# dimmer.net
KiCad netlist of a schematic drawn in Altium Designer
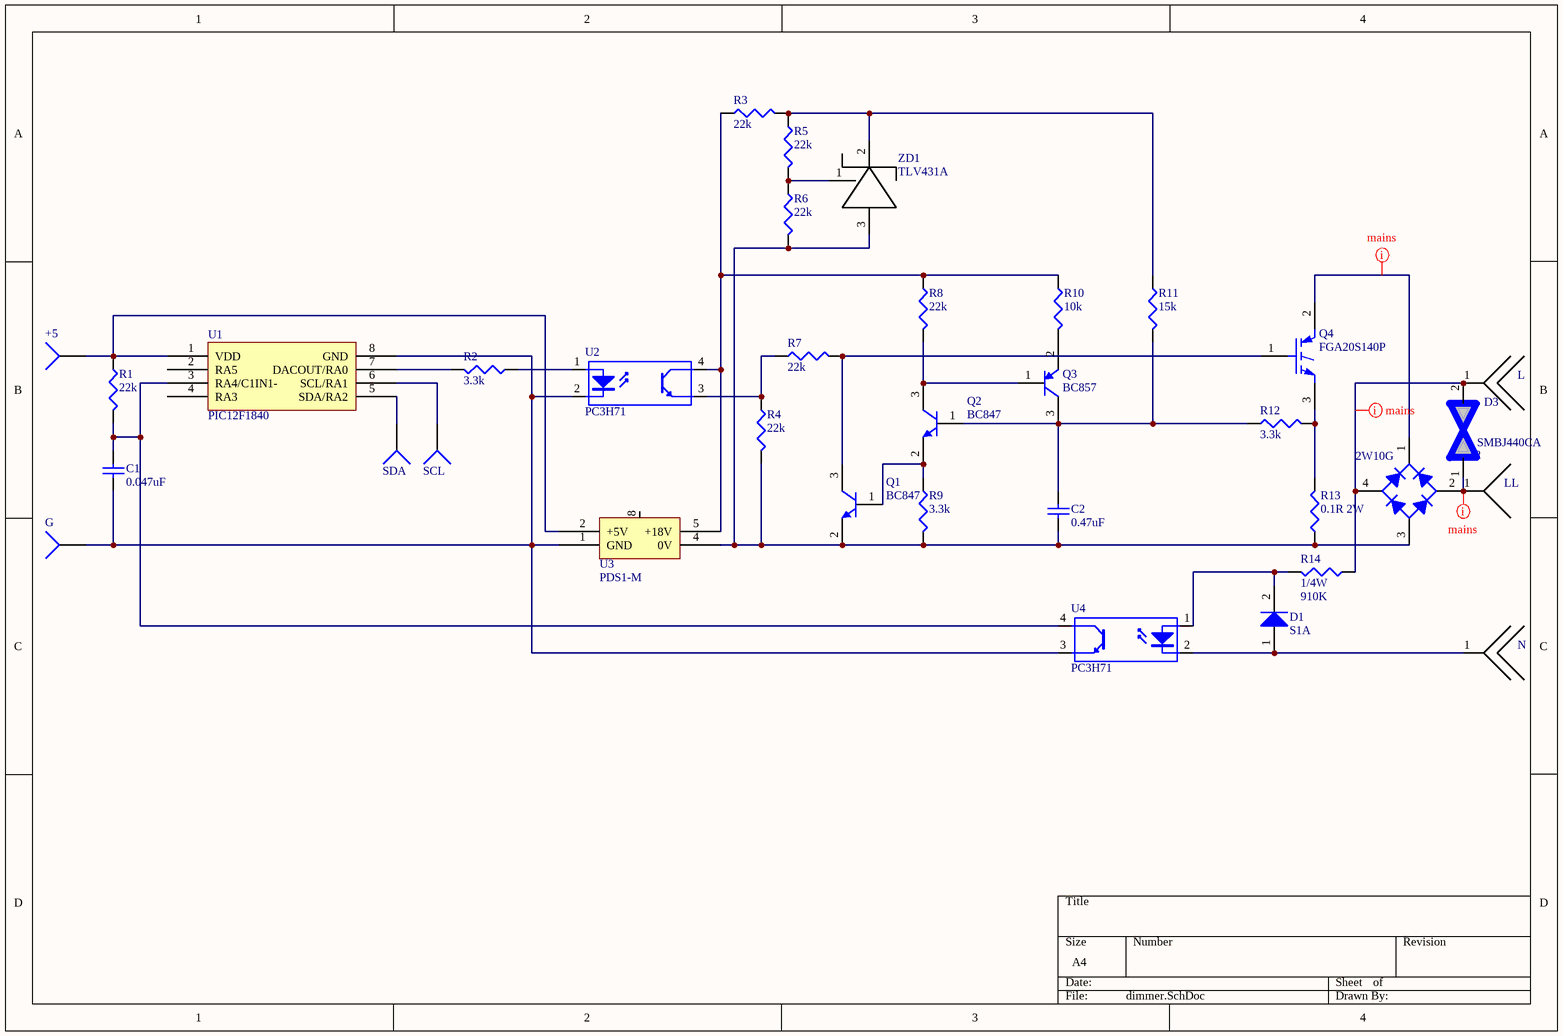
[diagram p0: dimmer.SchDoc]

(export (version "E")
  (design (tool "Eeschema 10.0.6"))
  (components
    (comp (ref "+5")
      (value "Socket")
      (footprint "PIN1")
      (fields (field (name "PUBLISHER") "Altium Limited"))
      (libsource (lib "misc") (part "Socket"))
    )
    (comp (ref "C1")
      (value "0.047uF")
      (footprint "1608[0603]")
      (description "Capacitor (Semiconductor SIM Model)")
      (fields (field (name "PUBLISHER") "Altium Limited"))
      (libsource (lib "Miscellaneous Devices") (part "Cap Semi"))
    )
    (comp (ref "C2")
      (value "0.47uF")
      (footprint "1608[0603]")
      (description "Capacitor (Semiconductor SIM Model)")
      (fields (field (name "PUBLISHER") "Altium Limited"))
      (libsource (lib "Miscellaneous Devices") (part "Cap Semi"))
    )
    (comp (ref "D1")
      (value "S1A")
      (footprint "DO-214AC")
      (description "Default Diode")
      (fields (field (name "PUBLISHER") "Altium Limited"))
      (libsource (lib "Miscellaneous Devices") (part "Diode"))
    )
    (comp (ref "D2")
      (value "2W10G")
      (footprint "2W10G")
      (description "Full Wave Diode Bridge")
      (fields (field (name "PUBLISHER") "Altium Limited"))
      (libsource (lib "Miscellaneous Devices") (part "Bridge1"))
    )
    (comp (ref "D3") (value "SMBJ440CA") (footprint "DO-214AA") (libsource (lib "tvs") (part "SMBJ440CA")))
    (comp (ref "G")
      (value "Socket")
      (footprint "PIN1")
      (fields (field (name "PUBLISHER") "Altium Limited"))
      (libsource (lib "misc") (part "Socket"))
    )
    (comp (ref "L") (value "PWRCON2X") (footprint "MAINSPIN2x") (libsource (lib "misc") (part "PWRCON2X")))
    (comp (ref "LL") (value "PWRCON") (footprint "MAINSPIN1") (libsource (lib "misc") (part "PWRCON")))
    (comp (ref "N") (value "PWRCON2X") (footprint "MAINSPIN3x") (libsource (lib "misc") (part "PWRCON2X")))
    (comp (ref "Q1")
      (value "BC847")
      (footprint "SOT-23_N")
      (description "NPN Bipolar Transistor")
      (fields (field (name "PUBLISHER") "Altium Limited"))
      (libsource (lib "Miscellaneous Devices") (part "NPN"))
    )
    (comp (ref "Q2")
      (value "BC847")
      (footprint "SOT-23_N")
      (description "NPN Bipolar Transistor")
      (fields (field (name "PUBLISHER") "Altium Limited"))
      (libsource (lib "Miscellaneous Devices") (part "NPN"))
    )
    (comp (ref "Q3")
      (value "BC857")
      (footprint "SOT-23_N")
      (description "PNP Bipolar Transistor")
      (fields (field (name "PUBLISHER") "Altium Limited"))
      (libsource (lib "Miscellaneous Devices") (part "PNP"))
    )
    (comp (ref "Q4")
      (value "FGA20S140P")
      (footprint "FGA20S140P")
      (description "Insulated Gate Bipolar Transistor (N-Channel)")
      (fields (field (name "PUBLISHER") "Altium Limited"))
      (libsource (lib "Miscellaneous Devices") (part "IGBT-N"))
    )
    (comp (ref "R1")
      (value "22k")
      (footprint "J1-0603")
      (description "Resistor")
      (fields (field (name "PUBLISHER") "Altium Limited"))
      (libsource (lib "Miscellaneous Devices") (part "Res3"))
    )
    (comp (ref "R2")
      (value "3.3k")
      (footprint "J1-0603")
      (description "Resistor")
      (fields (field (name "PUBLISHER") "Altium Limited"))
      (libsource (lib "Miscellaneous Devices") (part "Res3"))
    )
    (comp (ref "R3")
      (value "22k")
      (footprint "J1-0603")
      (description "Resistor")
      (fields (field (name "PUBLISHER") "Altium Limited"))
      (libsource (lib "Miscellaneous Devices") (part "Res3"))
    )
    (comp (ref "R4")
      (value "22k")
      (footprint "J1-0603")
      (description "Resistor")
      (fields (field (name "PUBLISHER") "Altium Limited"))
      (libsource (lib "Miscellaneous Devices") (part "Res3"))
    )
    (comp (ref "R5")
      (value "22k")
      (footprint "J1-0603")
      (description "Resistor")
      (fields (field (name "PUBLISHER") "Altium Limited"))
      (libsource (lib "Miscellaneous Devices") (part "Res3"))
    )
    (comp (ref "R6")
      (value "22k")
      (footprint "J1-0603")
      (description "Resistor")
      (fields (field (name "PUBLISHER") "Altium Limited"))
      (libsource (lib "Miscellaneous Devices") (part "Res3"))
    )
    (comp (ref "R7")
      (value "22k")
      (footprint "J1-0603")
      (description "Resistor")
      (fields (field (name "PUBLISHER") "Altium Limited"))
      (libsource (lib "Miscellaneous Devices") (part "Res3"))
    )
    (comp (ref "R8")
      (value "22k")
      (footprint "J1-0603")
      (description "Resistor")
      (fields (field (name "PUBLISHER") "Altium Limited"))
      (libsource (lib "Miscellaneous Devices") (part "Res3"))
    )
    (comp (ref "R9")
      (value "3.3k")
      (footprint "J1-0603")
      (description "Resistor")
      (fields (field (name "PUBLISHER") "Altium Limited"))
      (libsource (lib "Miscellaneous Devices") (part "Res3"))
    )
    (comp (ref "R10")
      (value "10k")
      (footprint "J1-0603")
      (description "Resistor")
      (fields (field (name "PUBLISHER") "Altium Limited"))
      (libsource (lib "Miscellaneous Devices") (part "Res3"))
    )
    (comp (ref "R11")
      (value "15k")
      (footprint "J1-0603")
      (description "Resistor")
      (fields (field (name "PUBLISHER") "Altium Limited"))
      (libsource (lib "Miscellaneous Devices") (part "Res3"))
    )
    (comp (ref "R12")
      (value "3.3k")
      (footprint "J1-0603")
      (description "Resistor")
      (fields (field (name "PUBLISHER") "Altium Limited"))
      (libsource (lib "Miscellaneous Devices") (part "Res3"))
    )
    (comp (ref "R13")
      (value "0.1R 2W")
      (footprint "R2512")
      (description "Resistor")
      (fields (field (name "PUBLISHER") "Altium Limited"))
      (libsource (lib "Miscellaneous Devices") (part "Res3"))
    )
    (comp (ref "R14")
      (value "1/4W")
      (footprint "R1206")
      (description "Resistor")
      (fields (field (name "ALTIUM_VALUE") "910K") (field (name "PUBLISHER") "Altium Limited"))
      (libsource (lib "Miscellaneous Devices") (part "Res3"))
    )
    (comp (ref "SCL")
      (value "Socket")
      (footprint "PIN1")
      (fields (field (name "PUBLISHER") "Altium Limited"))
      (libsource (lib "misc") (part "Socket"))
    )
    (comp (ref "SDA")
      (value "Socket")
      (footprint "PIN1")
      (fields (field (name "PUBLISHER") "Altium Limited"))
      (libsource (lib "misc") (part "Socket"))
    )
    (comp (ref "U1")
      (value "PIC12F1840")
      (footprint "SOIC150-8_N")
      (libsource (lib "pic") (part "PIC12F1840"))
    )
    (comp (ref "U2")
      (value "PC3H71")
      (footprint "PC3H71")
      (description "4-Pin Phototransistor Optocoupler")
      (fields (field (name "PUBLISHER") "Altium Limited"))
      (libsource (lib "Miscellaneous Devices") (part "Optoisolator1"))
    )
    (comp (ref "U3") (value "PDS1-M") (footprint "PDS1-M") (libsource (lib "DCDC") (part "PDS1-M")))
    (comp (ref "U4")
      (value "PC3H71")
      (footprint "PC3H71")
      (description "4-Pin Phototransistor Optocoupler")
      (fields (field (name "PUBLISHER") "Altium Limited"))
      (libsource (lib "Miscellaneous Devices") (part "Optoisolator1"))
    )
    (comp (ref "ZD1") (value "TLV431A") (footprint "SOT-23_N") (libsource (lib "misc") (part "TLV431A")))
  )
  (nets
    (net (code "1") (name "Net-(D1-A)") (class "Default")
      (node (ref "D1") (pin "1") (pinfunction "A_1") (pintype "passive"))
      (node (ref "N") (pin "1") (pintype "passive"))
      (node (ref "U4") (pin "2") (pinfunction "K_2") (pintype "passive"))
    )
    (net (code "2") (name "Net-(D1-K)") (class "Default")
      (node (ref "D1") (pin "2") (pinfunction "K_2") (pintype "passive"))
      (node (ref "R14") (pin "2") (pinfunction "2_2") (pintype "passive"))
      (node (ref "U4") (pin "1") (pinfunction "A_1") (pintype "passive"))
    )
    (net (code "3") (name "Net-(D2-A)") (class "Default")
      (node (ref "C2") (pin "1") (pinfunction "1_1") (pintype "passive"))
      (node (ref "D2") (pin "3") (pinfunction "A_3") (pintype "passive"))
      (node (ref "Q1") (pin "2") (pinfunction "E_2") (pintype "passive"))
      (node (ref "R13") (pin "1") (pinfunction "1_1") (pintype "passive"))
      (node (ref "R4") (pin "2") (pinfunction "2_2") (pintype "passive"))
      (node (ref "R6") (pin "2") (pinfunction "2_2") (pintype "passive"))
      (node (ref "R9") (pin "2") (pinfunction "2_2") (pintype "passive"))
      (node (ref "U3") (pin "4") (pinfunction "0V_4") (pintype "passive"))
      (node (ref "ZD1") (pin "3") (pinfunction "3_3") (pintype "passive"))
    )
    (net (code "4") (name "Net-(D2-C-Pad2)") (class "Default")
      (node (ref "D2") (pin "2") (pinfunction "C_2") (pintype "passive"))
      (node (ref "D3") (pin "1") (pinfunction "1_1") (pintype "passive"))
      (node (ref "LL") (pin "1") (pintype "passive"))
    )
    (net (code "5") (name "Net-(D2-C-Pad4)") (class "Default")
      (node (ref "D2") (pin "4") (pinfunction "C_4") (pintype "passive"))
      (node (ref "D3") (pin "2") (pinfunction "2_2") (pintype "passive"))
      (node (ref "L") (pin "1") (pintype "passive"))
      (node (ref "R14") (pin "1") (pinfunction "1_1") (pintype "passive"))
    )
    (net (code "6") (name "Net-(D2-K)") (class "Default")
      (node (ref "D2") (pin "1") (pinfunction "K_1") (pintype "passive"))
      (node (ref "Q4") (pin "2") (pinfunction "C_2") (pintype "passive"))
    )
    (net (code "7") (name "Net-(Q1-B)") (class "Default")
      (node (ref "Q1") (pin "1") (pinfunction "B_1") (pintype "passive"))
      (node (ref "Q2") (pin "2") (pinfunction "E_2") (pintype "passive"))
      (node (ref "R9") (pin "1") (pinfunction "1_1") (pintype "passive"))
    )
    (net (code "8") (name "Net-(Q1-C)") (class "Default")
      (node (ref "Q1") (pin "3") (pinfunction "C_3") (pintype "passive"))
      (node (ref "Q4") (pin "1") (pinfunction "G_1") (pintype "passive"))
      (node (ref "R7") (pin "2") (pinfunction "2_2") (pintype "passive"))
    )
    (net (code "9") (name "Net-(Q2-B)") (class "Default")
      (node (ref "C2") (pin "2") (pinfunction "2_2") (pintype "passive"))
      (node (ref "Q2") (pin "1") (pinfunction "B_1") (pintype "passive"))
      (node (ref "Q3") (pin "3") (pinfunction "C_3") (pintype "passive"))
      (node (ref "R11") (pin "2") (pinfunction "2_2") (pintype "passive"))
      (node (ref "R12") (pin "1") (pinfunction "1_1") (pintype "passive"))
    )
    (net (code "10") (name "Net-(Q2-C)") (class "Default")
      (node (ref "Q2") (pin "3") (pinfunction "C_3") (pintype "passive"))
      (node (ref "Q3") (pin "1") (pinfunction "B_1") (pintype "passive"))
      (node (ref "R8") (pin "2") (pinfunction "2_2") (pintype "passive"))
    )
    (net (code "11") (name "Net-(Q3-E)") (class "Default")
      (node (ref "Q3") (pin "2") (pinfunction "E_2") (pintype "passive"))
      (node (ref "R10") (pin "2") (pinfunction "2_2") (pintype "passive"))
    )
    (net (code "12") (name "Net-(Q4-E)") (class "Default")
      (node (ref "Q4") (pin "3") (pinfunction "E_3") (pintype "passive"))
      (node (ref "R12") (pin "2") (pinfunction "2_2") (pintype "passive"))
      (node (ref "R13") (pin "2") (pinfunction "2_2") (pintype "passive"))
    )
    (net (code "13") (name "Net-(R5-Pad2)") (class "Default")
      (node (ref "R5") (pin "2") (pinfunction "2_2") (pintype "passive"))
      (node (ref "R6") (pin "1") (pinfunction "1_1") (pintype "passive"))
      (node (ref "ZD1") (pin "1") (pinfunction "1_1") (pintype "passive"))
    )
    (net (code "14") (name "Net-(R11-Pad1)") (class "Default")
      (node (ref "R11") (pin "1") (pinfunction "1_1") (pintype "passive"))
      (node (ref "R3") (pin "2") (pinfunction "2_2") (pintype "passive"))
      (node (ref "R5") (pin "1") (pinfunction "1_1") (pintype "passive"))
      (node (ref "ZD1") (pin "2") (pinfunction "2_2") (pintype "passive"))
    )
    (net (code "15") (name "Net-(U1-DACOUT{slash}RA0)") (class "Default")
      (node (ref "R2") (pin "2") (pinfunction "2_2") (pintype "passive"))
      (node (ref "U1") (pin "7") (pinfunction "DACOUT/RA0_7") (pintype "passive"))
    )
    (net (code "16") (name "Net-(U1-GND)") (class "Default")
      (node (ref "C1") (pin "1") (pinfunction "1_1") (pintype "passive"))
      (node (ref "G") (pin "1") (pinfunction "1_1") (pintype "passive"))
      (node (ref "U1") (pin "8") (pinfunction "GND_8") (pintype "passive"))
      (node (ref "U2") (pin "2") (pinfunction "K_2") (pintype "passive"))
      (node (ref "U3") (pin "1") (pinfunction "GND_1") (pintype "passive"))
      (node (ref "U4") (pin "3") (pinfunction "E_3") (pintype "passive"))
    )
    (net (code "17") (name "Net-(U1-RA4{slash}C1IN1-)") (class "Default")
      (node (ref "C1") (pin "2") (pinfunction "2_2") (pintype "passive"))
      (node (ref "R1") (pin "2") (pinfunction "2_2") (pintype "passive"))
      (node (ref "U1") (pin "3") (pinfunction "RA4/C1IN1-_3") (pintype "passive"))
      (node (ref "U4") (pin "4") (pinfunction "C_4") (pintype "passive"))
    )
    (net (code "18") (name "Net-(U1-SCL{slash}RA1)") (class "Default")
      (node (ref "SCL") (pin "1") (pinfunction "1_1") (pintype "passive"))
      (node (ref "U1") (pin "6") (pinfunction "SCL/RA1_6") (pintype "passive"))
    )
    (net (code "19") (name "Net-(U1-SDA{slash}RA2)") (class "Default")
      (node (ref "SDA") (pin "1") (pinfunction "1_1") (pintype "passive"))
      (node (ref "U1") (pin "5") (pinfunction "SDA/RA2_5") (pintype "passive"))
    )
    (net (code "20") (name "Net-(U1-VDD)") (class "Default")
      (node (ref "+5") (pin "1") (pinfunction "1_1") (pintype "passive"))
      (node (ref "R1") (pin "1") (pinfunction "1_1") (pintype "passive"))
      (node (ref "U1") (pin "1") (pinfunction "VDD_1") (pintype "passive"))
      (node (ref "U3") (pin "2") (pinfunction "+5V_2") (pintype "passive"))
    )
    (net (code "21") (name "Net-(U2-A)") (class "Default")
      (node (ref "R2") (pin "1") (pinfunction "1_1") (pintype "passive"))
      (node (ref "U2") (pin "1") (pinfunction "A_1") (pintype "passive"))
    )
    (net (code "22") (name "Net-(U2-C)") (class "Default")
      (node (ref "R10") (pin "1") (pinfunction "1_1") (pintype "passive"))
      (node (ref "R3") (pin "1") (pinfunction "1_1") (pintype "passive"))
      (node (ref "R8") (pin "1") (pinfunction "1_1") (pintype "passive"))
      (node (ref "U2") (pin "4") (pinfunction "C_4") (pintype "passive"))
      (node (ref "U3") (pin "5") (pinfunction "+18V_5") (pintype "passive"))
    )
    (net (code "23") (name "Net-(U2-E)") (class "Default")
      (node (ref "R4") (pin "1") (pinfunction "1_1") (pintype "passive"))
      (node (ref "R7") (pin "1") (pinfunction "1_1") (pintype "passive"))
      (node (ref "U2") (pin "3") (pinfunction "E_3") (pintype "passive"))
    )
    (net (code "24") (name "unconnected-(U1-RA3-Pad4)") (class "Default")
      (node (ref "U1") (pin "4") (pinfunction "RA3_4") (pintype "passive"))
    )
    (net (code "25") (name "unconnected-(U1-RA5-Pad2)") (class "Default")
      (node (ref "U1") (pin "2") (pinfunction "RA5_2") (pintype "passive"))
    )
    (net (code "26") (name "unconnected-(U3-Pad8)") (class "Default")
      (node (ref "U3") (pin "8") (pintype "passive"))
    )
  )
)
